# UART.net
KiCad netlist of a schematic drawn in Altium Designer
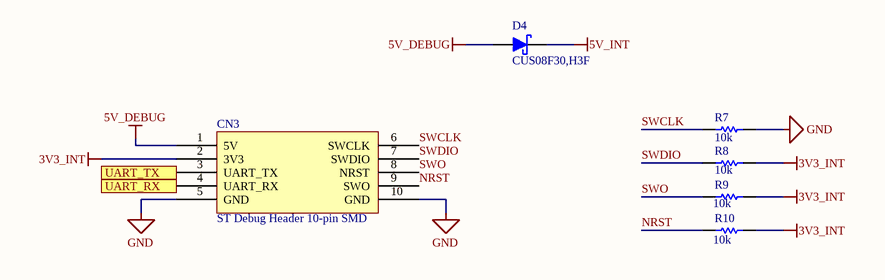
[diagram p0: UART.SchDoc]

(export (version "E")
  (design (tool "Eeschema 10.0.6"))
  (components
    (comp (ref "CN3")
      (value "ST Debug Header 10-pin SMD")
      (footprint "ST Debug Header 10-pin SMD-Footprint-1")
      (description "CONN HEADER SMD 10POS 2.54MM")
      (libsource (lib "AUVIC") (part "ST Debug Header 10-pin"))
    )
    (comp (ref "D4")
      (value "CUS08F30,H3F")
      (footprint "SC-76")
      (description "Diode Schottky 30V 800mA Surface Mount USC")
      (libsource (lib "") (part "Symbol_1"))
    )
    (comp (ref "R7")
      (value "10k")
      (footprint "RESC1608N(0603\")")
      (description "10kR, 1%, 1/10W, 0603 SMD")
      (fields (field (name "MADE BY") "Ashwin Sira"))
      (libsource (lib "AUVIC") (part "Symbol"))
    )
    (comp (ref "R8")
      (value "10k")
      (footprint "RESC1608N(0603\")")
      (description "10kR, 1%, 1/10W, 0603 SMD")
      (fields (field (name "MADE BY") "Ashwin Sira"))
      (libsource (lib "AUVIC") (part "Symbol"))
    )
    (comp (ref "R9")
      (value "10k")
      (footprint "RESC1608N(0603\")")
      (description "10kR, 1%, 1/10W, 0603 SMD")
      (fields (field (name "MADE BY") "Ashwin Sira"))
      (libsource (lib "AUVIC") (part "Symbol"))
    )
    (comp (ref "R10")
      (value "10k")
      (footprint "RESC1608N(0603\")")
      (description "10kR, 1%, 1/10W, 0603 SMD")
      (fields (field (name "MADE BY") "Ashwin Sira"))
      (libsource (lib "AUVIC") (part "Symbol"))
    )
  )
  (nets
    (net (code "1") (name "/NRST") (class "Default")
      (node (ref "CN3") (pin "9") (pinfunction "SWO_9") (pintype "passive"))
      (node (ref "R10") (pin "1") (pinfunction "1_1") (pintype "passive"))
    )
    (net (code "2") (name "/SWCLK") (class "Default")
      (node (ref "CN3") (pin "6") (pinfunction "SWCLK_6") (pintype "passive"))
      (node (ref "R7") (pin "1") (pinfunction "1_1") (pintype "passive"))
    )
    (net (code "3") (name "/SWDIO") (class "Default")
      (node (ref "CN3") (pin "7") (pinfunction "SWDIO_7") (pintype "passive"))
      (node (ref "R8") (pin "1") (pinfunction "1_1") (pintype "passive"))
    )
    (net (code "4") (name "/SWO") (class "Default")
      (node (ref "CN3") (pin "8") (pinfunction "NRST_8") (pintype "passive"))
      (node (ref "R9") (pin "1") (pinfunction "1_1") (pintype "passive"))
    )
    (net (code "5") (name "/UART_RX") (class "Default")
      (node (ref "CN3") (pin "4") (pinfunction "UART_RX_4") (pintype "passive"))
    )
    (net (code "6") (name "/UART_TX") (class "Default")
      (node (ref "CN3") (pin "3") (pinfunction "UART_TX_3") (pintype "passive"))
    )
    (net (code "7") (name "3V3_INT") (class "Default")
      (node (ref "CN3") (pin "2") (pinfunction "3V3_2") (pintype "passive"))
      (node (ref "R10") (pin "2") (pinfunction "2_2") (pintype "passive"))
      (node (ref "R8") (pin "2") (pinfunction "2_2") (pintype "passive"))
      (node (ref "R9") (pin "2") (pinfunction "2_2") (pintype "passive"))
    )
    (net (code "8") (name "5V_DEBUG") (class "Default")
      (node (ref "CN3") (pin "1") (pinfunction "5V_1") (pintype "passive"))
      (node (ref "D4") (pin "A") (pinfunction "Anode_A") (pintype "passive"))
    )
    (net (code "9") (name "5V_INT") (class "Default")
      (node (ref "D4") (pin "K") (pinfunction "Cathode_K") (pintype "passive"))
    )
    (net (code "10") (name "GND") (class "Default")
      (node (ref "CN3") (pin "10") (pinfunction "GND_10") (pintype "passive"))
      (node (ref "CN3") (pin "5") (pinfunction "GND_5") (pintype "passive"))
      (node (ref "R7") (pin "2") (pinfunction "2_2") (pintype "passive"))
    )
  )
)
